# NusbioV2_Board.net
KiCad netlist of a schematic drawn in EAGLE
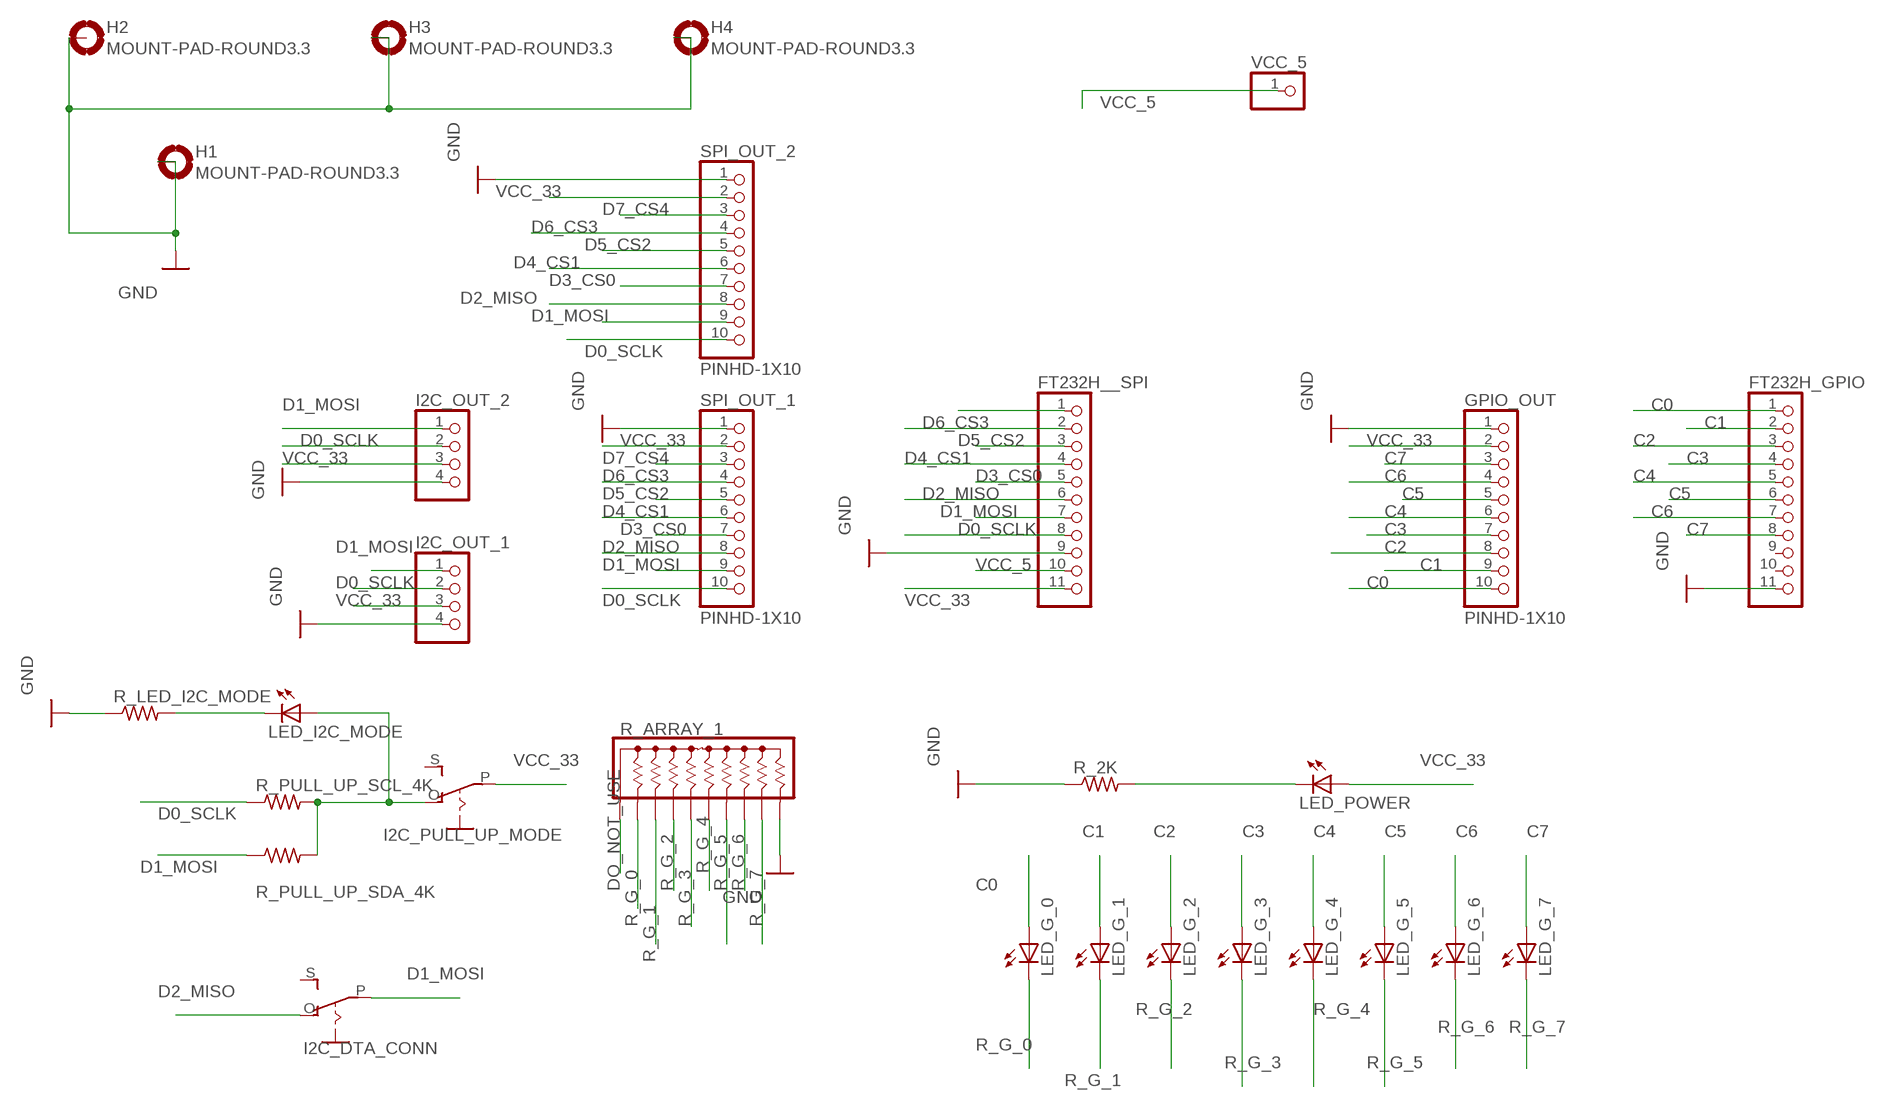
[diagram p0: schematic, sheet 1]

(export (version "E")
  (design (tool "Eeschema 10.0.6"))
  (components
    (comp (ref "FT232H_GPIO")
      (value "PINHD-1X11")
      (footprint "eagle-import:1X11")
      (libsource (lib "eagle-import") (part "PINHD-1X11"))
    )
    (comp (ref "FT232H__SPI")
      (value "PINHD-1X11")
      (footprint "eagle-import:1X11")
      (libsource (lib "eagle-import") (part "PINHD-1X11"))
    )
    (comp (ref "GPIO_OUT")
      (value "PINHD-1X10")
      (footprint "eagle-import:1X10-BIG")
      (libsource (lib "eagle-import") (part "PINHD-1X10"))
    )
    (comp (ref "H1")
      (value "MOUNT-PAD-ROUND3.3")
      (footprint "eagle-import:3,3-PAD")
      (libsource (lib "eagle-import") (part "MOUNT-PAD-ROUND3.3"))
    )
    (comp (ref "H2")
      (value "MOUNT-PAD-ROUND3.3")
      (footprint "eagle-import:3,3-PAD")
      (libsource (lib "eagle-import") (part "MOUNT-PAD-ROUND3.3"))
    )
    (comp (ref "H3")
      (value "MOUNT-PAD-ROUND3.3")
      (footprint "eagle-import:3,3-PAD")
      (libsource (lib "eagle-import") (part "MOUNT-PAD-ROUND3.3"))
    )
    (comp (ref "H4")
      (value "MOUNT-PAD-ROUND3.3")
      (footprint "eagle-import:3,3-PAD")
      (libsource (lib "eagle-import") (part "MOUNT-PAD-ROUND3.3"))
    )
    (comp (ref "I2C_DTA_CONN")
      (value "EG1218S")
      (footprint "eagle-import:EG1218")
      (libsource (lib "eagle-import") (part "EG1218S"))
    )
    (comp (ref "I2C_OUT_1")
      (value "PINHD-1X4")
      (footprint "eagle-import:1X04")
      (libsource (lib "eagle-import") (part "PINHD-1X4"))
    )
    (comp (ref "I2C_OUT_2")
      (value "PINHD-1X4")
      (footprint "eagle-import:1X04")
      (libsource (lib "eagle-import") (part "PINHD-1X4"))
    )
    (comp (ref "I2C_PULL_UP_MODE")
      (value "EG1218S")
      (footprint "eagle-import:EG1218")
      (libsource (lib "eagle-import") (part "EG1218S"))
    )
    (comp (ref "LED_G_0")
      (value "LEDSMT1206")
      (footprint "eagle-import:1206")
      (libsource (lib "eagle-import") (part "LEDSMT1206"))
    )
    (comp (ref "LED_G_1")
      (value "LEDSMT1206")
      (footprint "eagle-import:1206")
      (libsource (lib "eagle-import") (part "LEDSMT1206"))
    )
    (comp (ref "LED_G_2")
      (value "LEDSMT1206")
      (footprint "eagle-import:1206")
      (libsource (lib "eagle-import") (part "LEDSMT1206"))
    )
    (comp (ref "LED_G_3")
      (value "LEDSMT1206")
      (footprint "eagle-import:1206")
      (libsource (lib "eagle-import") (part "LEDSMT1206"))
    )
    (comp (ref "LED_G_4")
      (value "LEDSMT1206")
      (footprint "eagle-import:1206")
      (libsource (lib "eagle-import") (part "LEDSMT1206"))
    )
    (comp (ref "LED_G_5")
      (value "LEDSMT1206")
      (footprint "eagle-import:1206")
      (libsource (lib "eagle-import") (part "LEDSMT1206"))
    )
    (comp (ref "LED_G_6")
      (value "LEDSMT1206")
      (footprint "eagle-import:1206")
      (libsource (lib "eagle-import") (part "LEDSMT1206"))
    )
    (comp (ref "LED_G_7")
      (value "LEDSMT1206")
      (footprint "eagle-import:1206")
      (libsource (lib "eagle-import") (part "LEDSMT1206"))
    )
    (comp (ref "LED_I2C_MODE")
      (value "LEDSMT1206")
      (footprint "eagle-import:1206")
      (libsource (lib "eagle-import") (part "LEDSMT1206"))
    )
    (comp (ref "LED_POWER")
      (value "LEDSMT1206")
      (footprint "eagle-import:1206")
      (libsource (lib "eagle-import") (part "LEDSMT1206"))
    )
    (comp (ref "R_2K")
      (value "R-US_R1206")
      (footprint "eagle-import:R1206")
      (libsource (lib "eagle-import") (part "R-US_R1206"))
    )
    (comp (ref "R_ARRAY_1")
      (value "4610X")
      (footprint "eagle-import:SIP10")
      (libsource (lib "eagle-import") (part "4610X"))
    )
    (comp (ref "R_LED_I2C_MODE")
      (value "R-US_R1206")
      (footprint "eagle-import:R1206")
      (libsource (lib "eagle-import") (part "R-US_R1206"))
    )
    (comp (ref "R_PULL_UP_SCL_4K")
      (value "R-US_R1206")
      (footprint "eagle-import:R1206")
      (libsource (lib "eagle-import") (part "R-US_R1206"))
    )
    (comp (ref "R_PULL_UP_SDA_4K")
      (value "R-US_R1206")
      (footprint "eagle-import:R1206")
      (libsource (lib "eagle-import") (part "R-US_R1206"))
    )
    (comp (ref "SPI_OUT_1")
      (value "PINHD-1X10")
      (footprint "eagle-import:1X10-BIG")
      (libsource (lib "eagle-import") (part "PINHD-1X10"))
    )
    (comp (ref "SPI_OUT_2")
      (value "PINHD-1X10")
      (footprint "eagle-import:1X10-BIG")
      (libsource (lib "eagle-import") (part "PINHD-1X10"))
    )
    (comp (ref "VCC_5")
      (value "PINHD-1X1")
      (footprint "eagle-import:1X01")
      (libsource (lib "eagle-import") (part "PINHD-1X1"))
    )
  )
  (nets
    (net (code "1") (name "/C0") (class "Default")
      (node (ref "FT232H_GPIO") (pin "1") (pinfunction "1_1") (pintype "passive"))
      (node (ref "GPIO_OUT") (pin "10") (pinfunction "10_10") (pintype "passive"))
      (node (ref "LED_G_0") (pin "A") (pinfunction "A_A") (pintype "passive"))
    )
    (net (code "2") (name "/C1") (class "Default")
      (node (ref "FT232H_GPIO") (pin "2") (pinfunction "2_2") (pintype "passive"))
      (node (ref "GPIO_OUT") (pin "9") (pinfunction "9_9") (pintype "passive"))
      (node (ref "LED_G_1") (pin "A") (pinfunction "A_A") (pintype "passive"))
    )
    (net (code "3") (name "/C2") (class "Default")
      (node (ref "FT232H_GPIO") (pin "3") (pinfunction "3_3") (pintype "passive"))
      (node (ref "GPIO_OUT") (pin "8") (pinfunction "8_8") (pintype "passive"))
      (node (ref "LED_G_2") (pin "A") (pinfunction "A_A") (pintype "passive"))
    )
    (net (code "4") (name "/C3") (class "Default")
      (node (ref "FT232H_GPIO") (pin "4") (pinfunction "4_4") (pintype "passive"))
      (node (ref "GPIO_OUT") (pin "7") (pinfunction "7_7") (pintype "passive"))
      (node (ref "LED_G_3") (pin "A") (pinfunction "A_A") (pintype "passive"))
    )
    (net (code "5") (name "/C4") (class "Default")
      (node (ref "FT232H_GPIO") (pin "5") (pinfunction "5_5") (pintype "passive"))
      (node (ref "GPIO_OUT") (pin "6") (pinfunction "6_6") (pintype "passive"))
      (node (ref "LED_G_4") (pin "A") (pinfunction "A_A") (pintype "passive"))
    )
    (net (code "6") (name "/C5") (class "Default")
      (node (ref "FT232H_GPIO") (pin "6") (pinfunction "6_6") (pintype "passive"))
      (node (ref "GPIO_OUT") (pin "5") (pinfunction "5_5") (pintype "passive"))
      (node (ref "LED_G_5") (pin "A") (pinfunction "A_A") (pintype "passive"))
    )
    (net (code "7") (name "/C6") (class "Default")
      (node (ref "FT232H_GPIO") (pin "7") (pinfunction "7_7") (pintype "passive"))
      (node (ref "GPIO_OUT") (pin "4") (pinfunction "4_4") (pintype "passive"))
      (node (ref "LED_G_6") (pin "A") (pinfunction "A_A") (pintype "passive"))
    )
    (net (code "8") (name "/C7") (class "Default")
      (node (ref "FT232H_GPIO") (pin "8") (pinfunction "8_8") (pintype "passive"))
      (node (ref "GPIO_OUT") (pin "3") (pinfunction "3_3") (pintype "passive"))
      (node (ref "LED_G_7") (pin "A") (pinfunction "A_A") (pintype "passive"))
    )
    (net (code "9") (name "/D0_SCLK") (class "Default")
      (node (ref "FT232H__SPI") (pin "8") (pinfunction "8_8") (pintype "passive"))
      (node (ref "I2C_OUT_1") (pin "2") (pinfunction "2_2") (pintype "passive"))
      (node (ref "I2C_OUT_2") (pin "2") (pinfunction "2_2") (pintype "passive"))
      (node (ref "R_PULL_UP_SCL_4K") (pin "1") (pinfunction "1_1") (pintype "passive"))
      (node (ref "SPI_OUT_1") (pin "10") (pinfunction "10_10") (pintype "passive"))
      (node (ref "SPI_OUT_2") (pin "10") (pinfunction "10_10") (pintype "passive"))
    )
    (net (code "10") (name "/D1_MOSI") (class "Default")
      (node (ref "FT232H__SPI") (pin "7") (pinfunction "7_7") (pintype "passive"))
      (node (ref "I2C_DTA_CONN") (pin "P") (pinfunction "P_P") (pintype "passive"))
      (node (ref "I2C_OUT_1") (pin "1") (pinfunction "1_1") (pintype "passive"))
      (node (ref "I2C_OUT_2") (pin "1") (pinfunction "1_1") (pintype "passive"))
      (node (ref "R_PULL_UP_SDA_4K") (pin "1") (pinfunction "1_1") (pintype "passive"))
      (node (ref "SPI_OUT_1") (pin "9") (pinfunction "9_9") (pintype "passive"))
      (node (ref "SPI_OUT_2") (pin "9") (pinfunction "9_9") (pintype "passive"))
    )
    (net (code "11") (name "/D2_MISO") (class "Default")
      (node (ref "FT232H__SPI") (pin "6") (pinfunction "6_6") (pintype "passive"))
      (node (ref "I2C_DTA_CONN") (pin "O") (pinfunction "O_O") (pintype "passive"))
      (node (ref "SPI_OUT_1") (pin "8") (pinfunction "8_8") (pintype "passive"))
      (node (ref "SPI_OUT_2") (pin "8") (pinfunction "8_8") (pintype "passive"))
    )
    (net (code "12") (name "/D3_CS0") (class "Default")
      (node (ref "FT232H__SPI") (pin "5") (pinfunction "5_5") (pintype "passive"))
      (node (ref "SPI_OUT_1") (pin "7") (pinfunction "7_7") (pintype "passive"))
      (node (ref "SPI_OUT_2") (pin "7") (pinfunction "7_7") (pintype "passive"))
    )
    (net (code "13") (name "/D4_CS1") (class "Default")
      (node (ref "FT232H__SPI") (pin "4") (pinfunction "4_4") (pintype "passive"))
      (node (ref "SPI_OUT_1") (pin "6") (pinfunction "6_6") (pintype "passive"))
      (node (ref "SPI_OUT_2") (pin "6") (pinfunction "6_6") (pintype "passive"))
    )
    (net (code "14") (name "/D5_CS2") (class "Default")
      (node (ref "FT232H__SPI") (pin "3") (pinfunction "3_3") (pintype "passive"))
      (node (ref "SPI_OUT_1") (pin "5") (pinfunction "5_5") (pintype "passive"))
      (node (ref "SPI_OUT_2") (pin "5") (pinfunction "5_5") (pintype "passive"))
    )
    (net (code "15") (name "/D6_CS3") (class "Default")
      (node (ref "FT232H__SPI") (pin "2") (pinfunction "2_2") (pintype "passive"))
      (node (ref "SPI_OUT_1") (pin "4") (pinfunction "4_4") (pintype "passive"))
      (node (ref "SPI_OUT_2") (pin "4") (pinfunction "4_4") (pintype "passive"))
    )
    (net (code "16") (name "/D7_CS4") (class "Default")
      (node (ref "FT232H__SPI") (pin "1") (pinfunction "1_1") (pintype "passive"))
      (node (ref "SPI_OUT_1") (pin "3") (pinfunction "3_3") (pintype "passive"))
      (node (ref "SPI_OUT_2") (pin "3") (pinfunction "3_3") (pintype "passive"))
    )
    (net (code "17") (name "/DO_NOT_USE") (class "Default")
      (node (ref "R_ARRAY_1") (pin "1") (pinfunction "1_1") (pintype "passive"))
    )
    (net (code "18") (name "/R_G_0") (class "Default")
      (node (ref "LED_G_0") (pin "C") (pinfunction "C_C") (pintype "passive"))
      (node (ref "R_ARRAY_1") (pin "2") (pinfunction "2_2") (pintype "passive"))
    )
    (net (code "19") (name "/R_G_1") (class "Default")
      (node (ref "LED_G_1") (pin "C") (pinfunction "C_C") (pintype "passive"))
      (node (ref "R_ARRAY_1") (pin "3") (pinfunction "3_3") (pintype "passive"))
    )
    (net (code "20") (name "/R_G_2") (class "Default")
      (node (ref "LED_G_2") (pin "C") (pinfunction "C_C") (pintype "passive"))
      (node (ref "R_ARRAY_1") (pin "4") (pinfunction "4_4") (pintype "passive"))
    )
    (net (code "21") (name "/R_G_3") (class "Default")
      (node (ref "LED_G_3") (pin "C") (pinfunction "C_C") (pintype "passive"))
      (node (ref "R_ARRAY_1") (pin "5") (pinfunction "5_5") (pintype "passive"))
    )
    (net (code "22") (name "/R_G_4") (class "Default")
      (node (ref "LED_G_4") (pin "C") (pinfunction "C_C") (pintype "passive"))
      (node (ref "R_ARRAY_1") (pin "6") (pinfunction "6_6") (pintype "passive"))
    )
    (net (code "23") (name "/R_G_5") (class "Default")
      (node (ref "LED_G_5") (pin "C") (pinfunction "C_C") (pintype "passive"))
      (node (ref "R_ARRAY_1") (pin "7") (pinfunction "7_7") (pintype "passive"))
    )
    (net (code "24") (name "/R_G_6") (class "Default")
      (node (ref "LED_G_6") (pin "C") (pinfunction "C_C") (pintype "passive"))
      (node (ref "R_ARRAY_1") (pin "8") (pinfunction "8_8") (pintype "passive"))
    )
    (net (code "25") (name "/R_G_7") (class "Default")
      (node (ref "LED_G_7") (pin "C") (pinfunction "C_C") (pintype "passive"))
      (node (ref "R_ARRAY_1") (pin "9") (pinfunction "9_9") (pintype "passive"))
    )
    (net (code "26") (name "/VCC_5") (class "Default")
      (node (ref "FT232H__SPI") (pin "10") (pinfunction "10_10") (pintype "passive"))
      (node (ref "VCC_5") (pin "1") (pinfunction "1_1") (pintype "passive"))
    )
    (net (code "27") (name "/VCC_33") (class "Default")
      (node (ref "FT232H__SPI") (pin "11") (pinfunction "11_11") (pintype "passive"))
      (node (ref "GPIO_OUT") (pin "2") (pinfunction "2_2") (pintype "passive"))
      (node (ref "I2C_OUT_1") (pin "3") (pinfunction "3_3") (pintype "passive"))
      (node (ref "I2C_OUT_2") (pin "3") (pinfunction "3_3") (pintype "passive"))
      (node (ref "I2C_PULL_UP_MODE") (pin "P") (pinfunction "P_P") (pintype "passive"))
      (node (ref "LED_POWER") (pin "A") (pinfunction "A_A") (pintype "passive"))
      (node (ref "SPI_OUT_1") (pin "2") (pinfunction "2_2") (pintype "passive"))
      (node (ref "SPI_OUT_2") (pin "2") (pinfunction "2_2") (pintype "passive"))
    )
    (net (code "28") (name "GND") (class "Default")
      (node (ref "FT232H_GPIO") (pin "11") (pinfunction "11_11") (pintype "passive"))
      (node (ref "FT232H__SPI") (pin "9") (pinfunction "9_9") (pintype "passive"))
      (node (ref "GPIO_OUT") (pin "1") (pinfunction "1_1") (pintype "passive"))
      (node (ref "H1") (pin "B3,3") (pinfunction "MOUNT_B3,3") (pintype "passive"))
      (node (ref "H2") (pin "B3,3") (pinfunction "MOUNT_B3,3") (pintype "passive"))
      (node (ref "H3") (pin "B3,3") (pinfunction "MOUNT_B3,3") (pintype "passive"))
      (node (ref "H4") (pin "B3,3") (pinfunction "MOUNT_B3,3") (pintype "passive"))
      (node (ref "I2C_OUT_1") (pin "4") (pinfunction "4_4") (pintype "passive"))
      (node (ref "I2C_OUT_2") (pin "4") (pinfunction "4_4") (pintype "passive"))
      (node (ref "R_2K") (pin "1") (pinfunction "1_1") (pintype "passive"))
      (node (ref "R_ARRAY_1") (pin "10") (pinfunction "10_10") (pintype "passive"))
      (node (ref "R_LED_I2C_MODE") (pin "1") (pinfunction "1_1") (pintype "passive"))
      (node (ref "SPI_OUT_1") (pin "1") (pinfunction "1_1") (pintype "passive"))
      (node (ref "SPI_OUT_2") (pin "1") (pinfunction "1_1") (pintype "passive"))
    )
    (net (code "29") (name "Net-(I2C_PULL_UP_MODE-PadO)") (class "Default")
      (node (ref "I2C_PULL_UP_MODE") (pin "O") (pinfunction "O_O") (pintype "passive"))
      (node (ref "LED_I2C_MODE") (pin "A") (pinfunction "A_A") (pintype "passive"))
      (node (ref "R_PULL_UP_SCL_4K") (pin "2") (pinfunction "2_2") (pintype "passive"))
      (node (ref "R_PULL_UP_SDA_4K") (pin "2") (pinfunction "2_2") (pintype "passive"))
    )
    (net (code "30") (name "Net-(LED_I2C_MODE-PadC)") (class "Default")
      (node (ref "LED_I2C_MODE") (pin "C") (pinfunction "C_C") (pintype "passive"))
      (node (ref "R_LED_I2C_MODE") (pin "2") (pinfunction "2_2") (pintype "passive"))
    )
    (net (code "31") (name "Net-(LED_POWER-PadC)") (class "Default")
      (node (ref "LED_POWER") (pin "C") (pinfunction "C_C") (pintype "passive"))
      (node (ref "R_2K") (pin "2") (pinfunction "2_2") (pintype "passive"))
    )
    (net (code "32") (name "unconnected-(FT232H_GPIO-Pad9)") (class "Default")
      (node (ref "FT232H_GPIO") (pin "9") (pinfunction "9_9") (pintype "passive"))
    )
    (net (code "33") (name "unconnected-(FT232H_GPIO-Pad10)") (class "Default")
      (node (ref "FT232H_GPIO") (pin "10") (pinfunction "10_10") (pintype "passive"))
    )
    (net (code "34") (name "unconnected-(I2C_DTA_CONN-PadS)") (class "Default")
      (node (ref "I2C_DTA_CONN") (pin "S") (pinfunction "S_S") (pintype "passive"))
    )
    (net (code "35") (name "unconnected-(I2C_PULL_UP_MODE-PadS)") (class "Default")
      (node (ref "I2C_PULL_UP_MODE") (pin "S") (pinfunction "S_S") (pintype "passive"))
    )
  )
)
